# VL6180.net
KiCad netlist of a schematic drawn in EAGLE
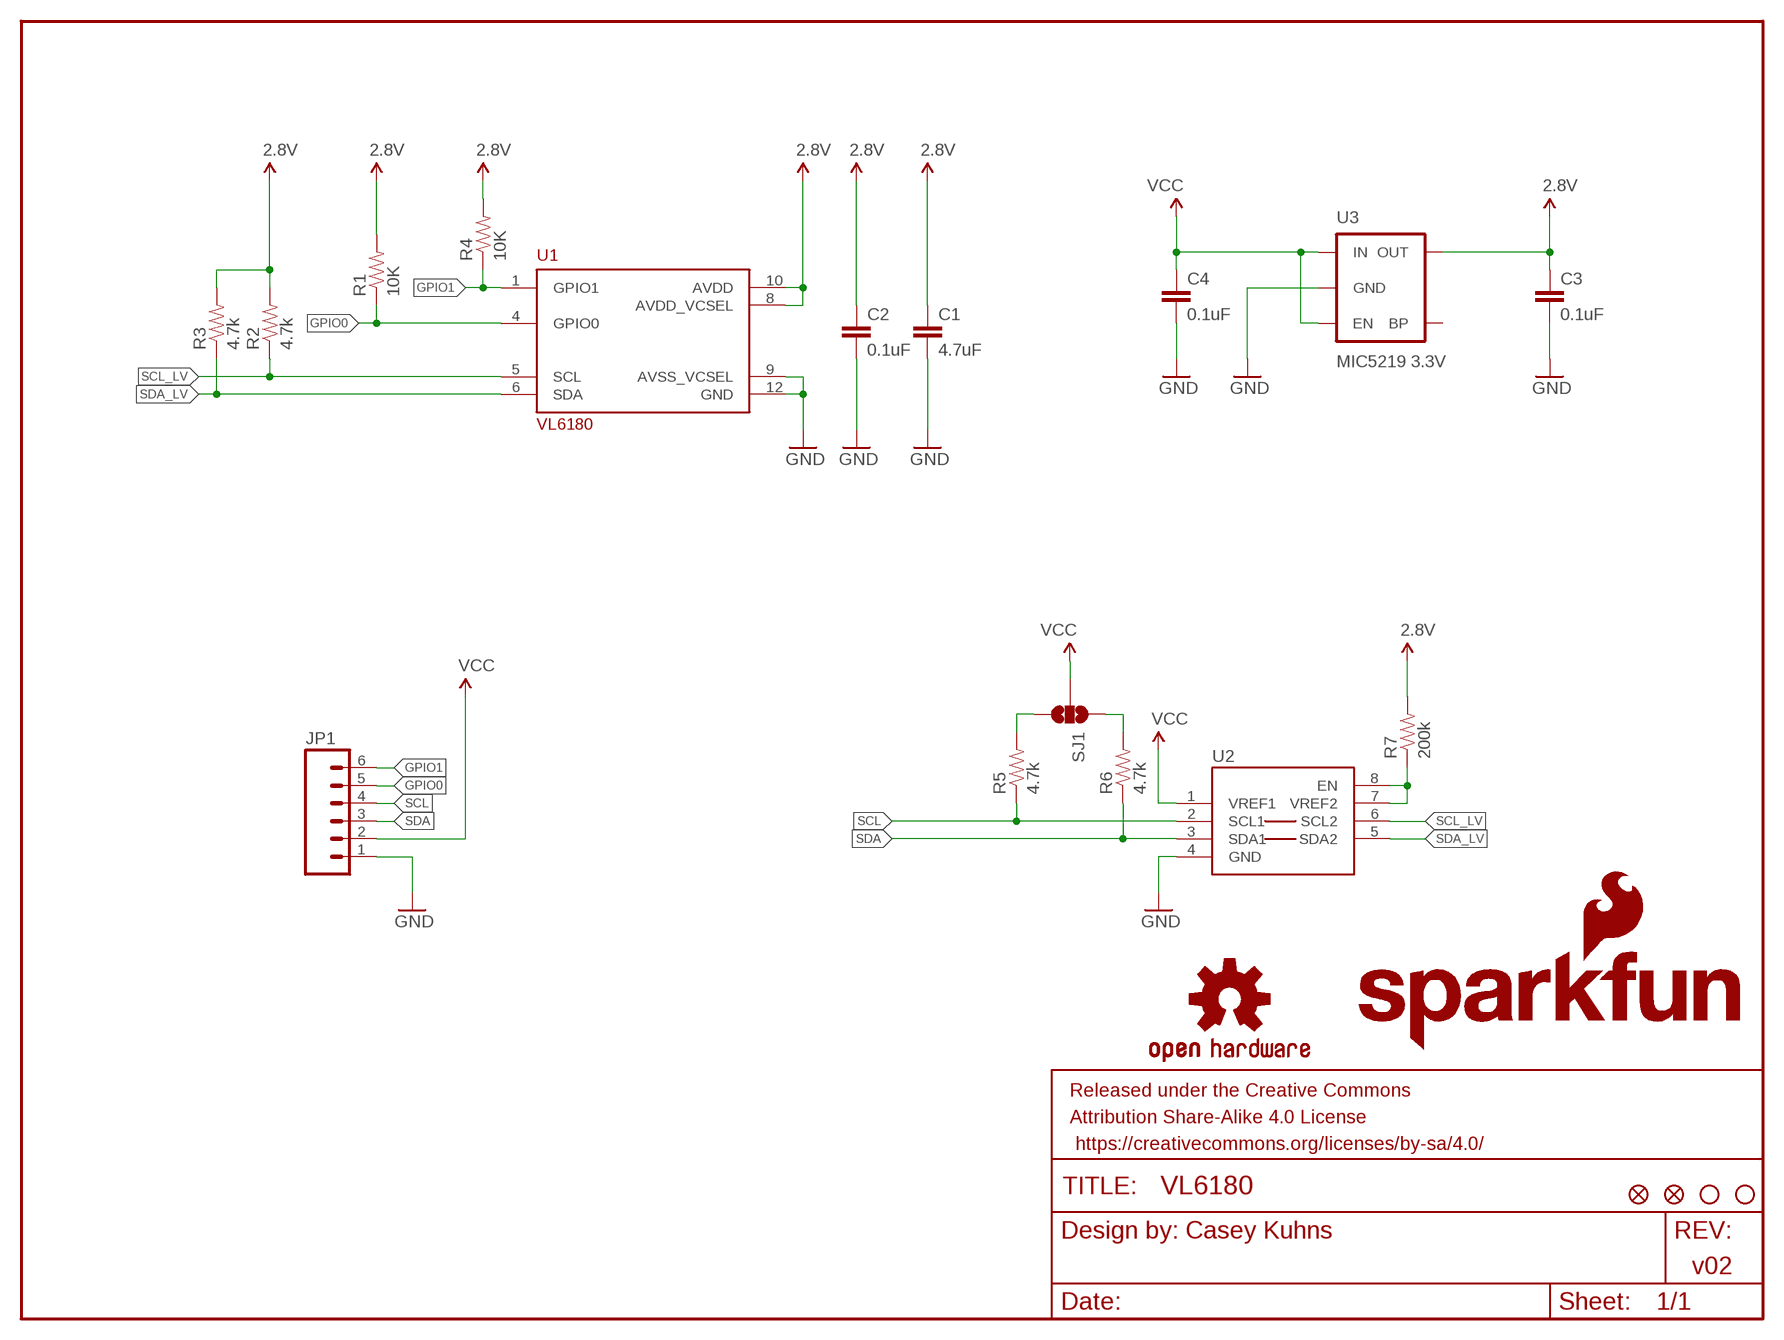
[diagram p0: schematic, sheet 1]

(export (version "E")
  (design (tool "Eeschema 10.0.6"))
  (components
    (comp (ref "C1")
      (value "4.7uF")
      (footprint "eagle-import:0603-CAP")
      (libsource (lib "eagle-import") (part "4.7UF-6.3V-10%(0603)0603"))
    )
    (comp (ref "C2")
      (value "0.1uF")
      (footprint "eagle-import:0603-CAP")
      (libsource (lib "eagle-import") (part "0.1UF-25V(+80/-20%)(0603)"))
    )
    (comp (ref "C3")
      (value "0.1uF")
      (footprint "eagle-import:0603-CAP")
      (libsource (lib "eagle-import") (part "0.1UF-25V(+80/-20%)(0603)"))
    )
    (comp (ref "C4")
      (value "0.1uF")
      (footprint "eagle-import:0603-CAP")
      (libsource (lib "eagle-import") (part "0.1UF-25V(+80/-20%)(0603)"))
    )
    (comp (ref "FID1")
      (value "FIDUCIAL1X2")
      (footprint "eagle-import:FIDUCIAL-1X2")
      (libsource (lib "eagle-import") (part "FIDUCIAL1X2"))
    )
    (comp (ref "FID2")
      (value "FIDUCIAL1X2")
      (footprint "eagle-import:FIDUCIAL-1X2")
      (libsource (lib "eagle-import") (part "FIDUCIAL1X2"))
    )
    (comp (ref "FRAME1")
      (value "FRAME-LETTER")
      (footprint "eagle-import:CREATIVE_COMMONS")
      (libsource (lib "eagle-import") (part "FRAME-LETTER"))
    )
    (comp (ref "JP1")
      (value "M06SIP")
      (footprint "eagle-import:1X06")
      (libsource (lib "eagle-import") (part "M06SIP"))
    )
    (comp (ref "LOGO1")
      (value "SFE_LOGO_NAME_FLAME.1_INCH")
      (footprint "eagle-import:SFE_LOGO_NAME_FLAME_.1")
      (libsource (lib "eagle-import") (part "SFE_LOGO_NAME_FLAME.1_INCH"))
    )
    (comp (ref "LOGO2")
      (value "OSHW-LOGOS")
      (footprint "eagle-import:OSHW-LOGO-S")
      (libsource (lib "eagle-import") (part "OSHW-LOGOS"))
    )
    (comp (ref "R1")
      (value "10K")
      (footprint "eagle-import:0603-RES")
      (libsource (lib "eagle-import") (part "10KOHM1/10W1%(0603)0603"))
    )
    (comp (ref "R2")
      (value "4.7k")
      (footprint "eagle-import:0603")
      (libsource (lib "eagle-import") (part "4.7KOHM1/10W1%(0603)"))
    )
    (comp (ref "R3")
      (value "4.7k")
      (footprint "eagle-import:0603")
      (libsource (lib "eagle-import") (part "4.7KOHM1/10W1%(0603)"))
    )
    (comp (ref "R4")
      (value "10K")
      (footprint "eagle-import:0603-RES")
      (libsource (lib "eagle-import") (part "10KOHM1/10W1%(0603)0603"))
    )
    (comp (ref "R5")
      (value "4.7k")
      (footprint "eagle-import:0603")
      (libsource (lib "eagle-import") (part "4.7KOHM1/10W1%(0603)"))
    )
    (comp (ref "R6")
      (value "4.7k")
      (footprint "eagle-import:0603")
      (libsource (lib "eagle-import") (part "4.7KOHM1/10W1%(0603)"))
    )
    (comp (ref "R7")
      (value "200k")
      (footprint "eagle-import:0603-RES")
      (libsource (lib "eagle-import") (part "200KOHM1/10W1%(0603)200K"))
    )
    (comp (ref "SJ1")
      (value "SOLDERJUMPER_2WAYPASTE1&2&3")
      (footprint "eagle-import:SJ_3_PASTE1&2&3")
      (libsource (lib "eagle-import") (part "SOLDERJUMPER_2WAYPASTE1&2&3"))
    )
    (comp (ref "STANDOFF1")
      (value "STAND-OFF")
      (footprint "eagle-import:STAND-OFF")
      (libsource (lib "eagle-import") (part "STAND-OFF"))
    )
    (comp (ref "STANDOFF2")
      (value "STAND-OFF")
      (footprint "eagle-import:STAND-OFF")
      (libsource (lib "eagle-import") (part "STAND-OFF"))
    )
    (comp (ref "U1")
      (value "VL6180")
      (footprint "eagle-import:VL6180")
      (libsource (lib "eagle-import") (part "VL6180"))
    )
    (comp (ref "U2")
      (value "PCA9306")
      (footprint "eagle-import:PSOP-8")
      (libsource (lib "eagle-import") (part "PCA9306"))
    )
    (comp (ref "U3")
      (value "MIC5219 3.3V")
      (footprint "eagle-import:SOT23-5")
      (libsource (lib "eagle-import") (part "V_REG_MIC52193.3V"))
    )
  )
  (nets
    (net (code "1") (name "2.8V") (class "Default")
      (node (ref "C1") (pin "1") (pinfunction "1_1") (pintype "passive"))
      (node (ref "C2") (pin "1") (pinfunction "1_1") (pintype "passive"))
      (node (ref "C3") (pin "1") (pinfunction "1_1") (pintype "passive"))
      (node (ref "R1") (pin "2") (pinfunction "2_2") (pintype "passive"))
      (node (ref "R2") (pin "2") (pinfunction "2_2") (pintype "passive"))
      (node (ref "R3") (pin "2") (pinfunction "2_2") (pintype "passive"))
      (node (ref "R4") (pin "2") (pinfunction "2_2") (pintype "passive"))
      (node (ref "R7") (pin "2") (pinfunction "2_2") (pintype "passive"))
      (node (ref "U1") (pin "10") (pinfunction "AVDD_10") (pintype "bidirectional"))
      (node (ref "U1") (pin "8") (pinfunction "AVDD_VCSEL_8") (pintype "bidirectional"))
      (node (ref "U3") (pin "5") (pinfunction "OUT_5") (pintype "passive"))
    )
    (net (code "2") (name "GND") (class "Default")
      (node (ref "C1") (pin "2") (pinfunction "2_2") (pintype "passive"))
      (node (ref "C2") (pin "2") (pinfunction "2_2") (pintype "passive"))
      (node (ref "C3") (pin "2") (pinfunction "2_2") (pintype "passive"))
      (node (ref "C4") (pin "2") (pinfunction "2_2") (pintype "passive"))
      (node (ref "JP1") (pin "1") (pinfunction "1_1") (pintype "passive"))
      (node (ref "U1") (pin "12") (pinfunction "GND_12") (pintype "bidirectional"))
      (node (ref "U1") (pin "9") (pinfunction "AVSS_VCSEL_9") (pintype "bidirectional"))
      (node (ref "U2") (pin "4") (pinfunction "GND_4") (pintype "bidirectional"))
      (node (ref "U3") (pin "2") (pinfunction "GND_2") (pintype "input"))
    )
    (net (code "3") (name "GPIO0") (class "Default")
      (node (ref "JP1") (pin "5") (pinfunction "5_5") (pintype "passive"))
      (node (ref "R1") (pin "1") (pinfunction "1_1") (pintype "passive"))
      (node (ref "U1") (pin "4") (pinfunction "GPIO0_4") (pintype "bidirectional"))
    )
    (net (code "4") (name "GPIO1") (class "Default")
      (node (ref "JP1") (pin "6") (pinfunction "6_6") (pintype "passive"))
      (node (ref "R4") (pin "1") (pinfunction "1_1") (pintype "passive"))
      (node (ref "U1") (pin "1") (pinfunction "GPIO1_1") (pintype "bidirectional"))
    )
    (net (code "5") (name "Net-(R5-Pad2)") (class "Default")
      (node (ref "R5") (pin "2") (pinfunction "2_2") (pintype "passive"))
      (node (ref "SJ1") (pin "3") (pinfunction "3_3") (pintype "passive"))
    )
    (net (code "6") (name "Net-(R6-Pad2)") (class "Default")
      (node (ref "R6") (pin "2") (pinfunction "2_2") (pintype "passive"))
      (node (ref "SJ1") (pin "1") (pinfunction "1_1") (pintype "passive"))
    )
    (net (code "7") (name "Net-(U2-EN)") (class "Default")
      (node (ref "R7") (pin "1") (pinfunction "1_1") (pintype "passive"))
      (node (ref "U2") (pin "7") (pinfunction "VREF2_7") (pintype "bidirectional"))
      (node (ref "U2") (pin "8") (pinfunction "EN_8") (pintype "bidirectional"))
    )
    (net (code "8") (name "SCL") (class "Default")
      (node (ref "JP1") (pin "4") (pinfunction "4_4") (pintype "passive"))
      (node (ref "R5") (pin "1") (pinfunction "1_1") (pintype "passive"))
      (node (ref "U2") (pin "2") (pinfunction "SCL1_2") (pintype "bidirectional"))
    )
    (net (code "9") (name "SCL_LV") (class "Default")
      (node (ref "R2") (pin "1") (pinfunction "1_1") (pintype "passive"))
      (node (ref "U1") (pin "5") (pinfunction "SCL_5") (pintype "bidirectional"))
      (node (ref "U2") (pin "6") (pinfunction "SCL2_6") (pintype "bidirectional"))
    )
    (net (code "10") (name "SDA") (class "Default")
      (node (ref "JP1") (pin "3") (pinfunction "3_3") (pintype "passive"))
      (node (ref "R6") (pin "1") (pinfunction "1_1") (pintype "passive"))
      (node (ref "U2") (pin "3") (pinfunction "SDA1_3") (pintype "bidirectional"))
    )
    (net (code "11") (name "SDA_LV") (class "Default")
      (node (ref "R3") (pin "1") (pinfunction "1_1") (pintype "passive"))
      (node (ref "U1") (pin "6") (pinfunction "SDA_6") (pintype "bidirectional"))
      (node (ref "U2") (pin "5") (pinfunction "SDA2_5") (pintype "bidirectional"))
    )
    (net (code "12") (name "VCC") (class "Default")
      (node (ref "C4") (pin "1") (pinfunction "1_1") (pintype "passive"))
      (node (ref "JP1") (pin "2") (pinfunction "2_2") (pintype "passive"))
      (node (ref "SJ1") (pin "2") (pinfunction "2_2") (pintype "passive"))
      (node (ref "U2") (pin "1") (pinfunction "VREF1_1") (pintype "bidirectional"))
      (node (ref "U3") (pin "1") (pinfunction "IN_1") (pintype "input"))
      (node (ref "U3") (pin "3") (pinfunction "EN_3") (pintype "input"))
    )
    (net (code "13") (name "unconnected-(U3-BP-Pad4)") (class "Default")
      (node (ref "U3") (pin "4") (pinfunction "BP_4") (pintype "input"))
    )
  )
)
